# adc_dev.net
KiCad netlist of a schematic drawn in EAGLE
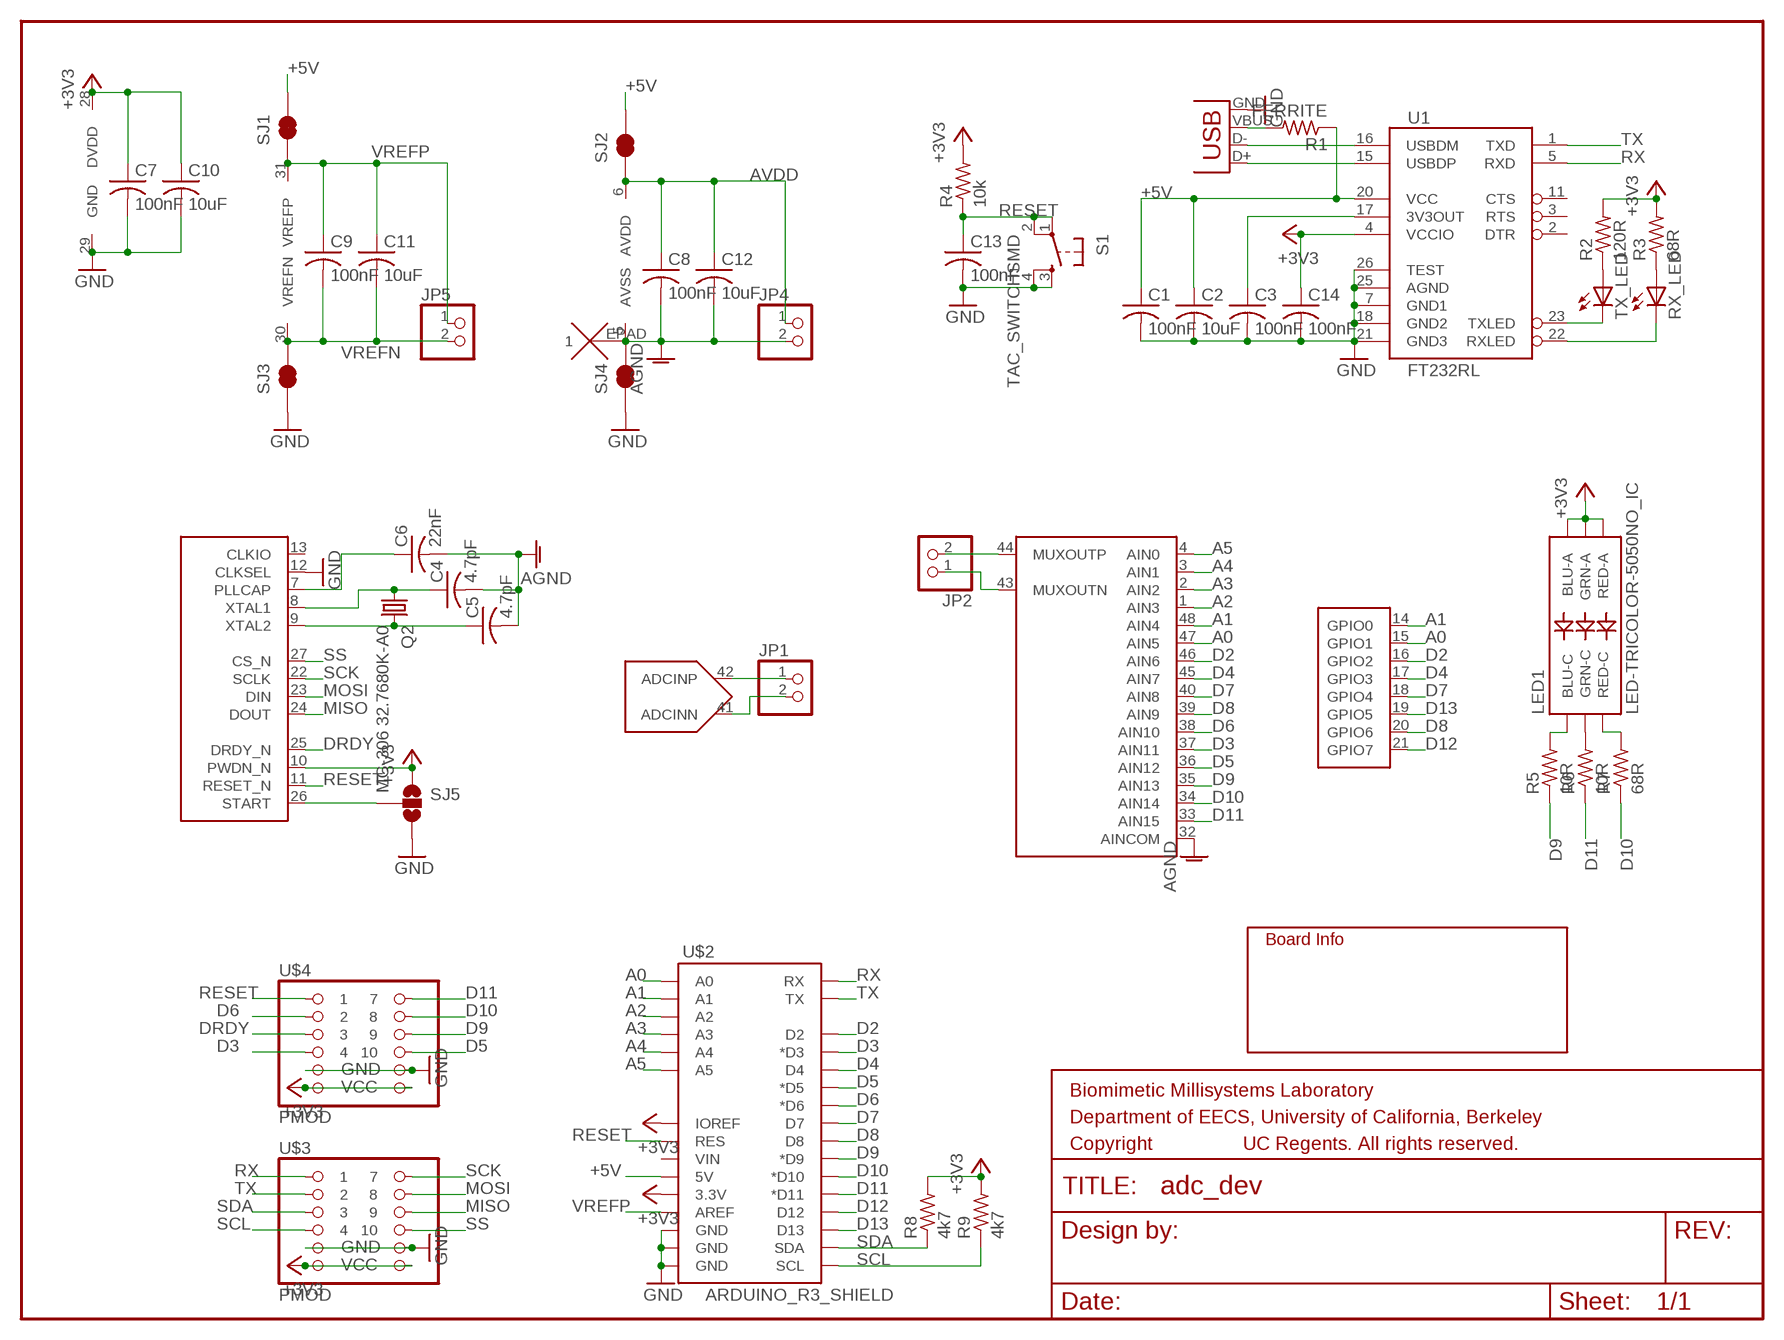
[diagram p0: schematic, sheet 1]

(export (version "E")
  (design (tool "Eeschema 10.0.6"))
  (components
    (comp (ref "C1")
      (value "100nF")
      (footprint "eagle-import:C0603")
      (libsource (lib "eagle-import") (part "C-USC0603"))
    )
    (comp (ref "C2")
      (value "10uF")
      (footprint "eagle-import:C0603")
      (libsource (lib "eagle-import") (part "C-USC0603"))
    )
    (comp (ref "C3")
      (value "100nF")
      (footprint "eagle-import:C0603")
      (libsource (lib "eagle-import") (part "C-USC0603"))
    )
    (comp (ref "C4")
      (value "4.7pF")
      (footprint "eagle-import:C0603")
      (libsource (lib "eagle-import") (part "C-USC0603"))
    )
    (comp (ref "C5")
      (value "4.7pF")
      (footprint "eagle-import:C0603")
      (libsource (lib "eagle-import") (part "C-USC0603"))
    )
    (comp (ref "C6")
      (value "22nF")
      (footprint "eagle-import:C0603")
      (libsource (lib "eagle-import") (part "C-USC0603"))
    )
    (comp (ref "C7")
      (value "100nF")
      (footprint "eagle-import:C0603")
      (libsource (lib "eagle-import") (part "C-USC0603"))
    )
    (comp (ref "C8")
      (value "100nF")
      (footprint "eagle-import:C0603")
      (libsource (lib "eagle-import") (part "C-USC0603"))
    )
    (comp (ref "C9")
      (value "100nF")
      (footprint "eagle-import:C0603")
      (libsource (lib "eagle-import") (part "C-USC0603"))
    )
    (comp (ref "C10")
      (value "10uF")
      (footprint "eagle-import:C0603")
      (libsource (lib "eagle-import") (part "C-USC0603"))
    )
    (comp (ref "C11")
      (value "10uF")
      (footprint "eagle-import:C0603")
      (libsource (lib "eagle-import") (part "C-USC0603"))
    )
    (comp (ref "C12")
      (value "10uF")
      (footprint "eagle-import:C0603")
      (libsource (lib "eagle-import") (part "C-USC0603"))
    )
    (comp (ref "C13")
      (value "100nF")
      (footprint "eagle-import:C0603")
      (libsource (lib "eagle-import") (part "C-USC0603"))
    )
    (comp (ref "C14")
      (value "100nF")
      (footprint "eagle-import:C0603")
      (libsource (lib "eagle-import") (part "C-USC0603"))
    )
    (comp (ref "JP1")
      (value "PINHD-1X2")
      (footprint "eagle-import:1X02")
      (libsource (lib "eagle-import") (part "PINHD-1X2"))
    )
    (comp (ref "JP2")
      (value "PINHD-1X2")
      (footprint "eagle-import:1X02")
      (libsource (lib "eagle-import") (part "PINHD-1X2"))
    )
    (comp (ref "JP3")
      (value "USBSMD")
      (footprint "eagle-import:USB-MINIB")
      (libsource (lib "eagle-import") (part "USBSMD"))
    )
    (comp (ref "JP4")
      (value "PINHD-1X2")
      (footprint "eagle-import:1X02")
      (libsource (lib "eagle-import") (part "PINHD-1X2"))
    )
    (comp (ref "JP5")
      (value "PINHD-1X2")
      (footprint "eagle-import:1X02")
      (libsource (lib "eagle-import") (part "PINHD-1X2"))
    )
    (comp (ref "LED1")
      (value "LED-TRICOLOR-5050NO_IC")
      (footprint "eagle-import:LED-TRICOLOR-5050")
      (libsource (lib "eagle-import") (part "LED-TRICOLOR-5050NO_IC"))
    )
    (comp (ref "Q2")
      (value "MC-306 32.7680K-A0")
      (footprint "eagle-import:MC-306")
      (fields (field (name "MPN") "MC-306 60.0KHZ  100PPM ,12.5PF"))
      (libsource (lib "eagle-import") (part "MC-306"))
    )
    (comp (ref "R1")
      (value "FERRITE")
      (footprint "eagle-import:R0603")
      (libsource (lib "eagle-import") (part "R-US_R0603"))
    )
    (comp (ref "R2")
      (value "120R")
      (footprint "eagle-import:R0603")
      (libsource (lib "eagle-import") (part "R-US_R0603"))
    )
    (comp (ref "R3")
      (value "68R")
      (footprint "eagle-import:R0603")
      (libsource (lib "eagle-import") (part "R-US_R0603"))
    )
    (comp (ref "R4")
      (value "10k")
      (footprint "eagle-import:R0603")
      (libsource (lib "eagle-import") (part "R-US_R0603"))
    )
    (comp (ref "R5")
      (value "10R")
      (footprint "eagle-import:R0603")
      (libsource (lib "eagle-import") (part "R-US_R0603"))
    )
    (comp (ref "R6")
      (value "10R")
      (footprint "eagle-import:R0603")
      (libsource (lib "eagle-import") (part "R-US_R0603"))
    )
    (comp (ref "R7")
      (value "68R")
      (footprint "eagle-import:R0603")
      (libsource (lib "eagle-import") (part "R-US_R0603"))
    )
    (comp (ref "R8")
      (value "4k7")
      (footprint "eagle-import:R0603")
      (libsource (lib "eagle-import") (part "R-US_R0603"))
    )
    (comp (ref "R9")
      (value "4k7")
      (footprint "eagle-import:R0603")
      (libsource (lib "eagle-import") (part "R-US_R0603"))
    )
    (comp (ref "RX_LED")
      (value "LEDCHIPLED_0603")
      (footprint "eagle-import:CHIPLED_0603")
      (libsource (lib "eagle-import") (part "LEDCHIPLED_0603"))
    )
    (comp (ref "S1")
      (value "TAC_SWITCHSMD")
      (footprint "eagle-import:TACTILE_SWITCH_SMD")
      (libsource (lib "eagle-import") (part "TAC_SWITCHSMD"))
    )
    (comp (ref "SJ1")
      (value "JUMPER-PAD-2-NC_BY_TRACE")
      (footprint "eagle-import:PAD-JUMPER-2-NC_BY_TRACE_YES_SILK")
      (libsource (lib "eagle-import") (part "JUMPER-PAD-2-NC_BY_TRACE"))
    )
    (comp (ref "SJ2")
      (value "JUMPER-PAD-2-NC_BY_TRACE")
      (footprint "eagle-import:PAD-JUMPER-2-NC_BY_TRACE_YES_SILK")
      (libsource (lib "eagle-import") (part "JUMPER-PAD-2-NC_BY_TRACE"))
    )
    (comp (ref "SJ3")
      (value "JUMPER-PAD-2-NC_BY_TRACE")
      (footprint "eagle-import:PAD-JUMPER-2-NC_BY_TRACE_YES_SILK")
      (libsource (lib "eagle-import") (part "JUMPER-PAD-2-NC_BY_TRACE"))
    )
    (comp (ref "SJ4")
      (value "JUMPER-PAD-2-NC_BY_TRACE")
      (footprint "eagle-import:PAD-JUMPER-2-NC_BY_TRACE_YES_SILK")
      (libsource (lib "eagle-import") (part "JUMPER-PAD-2-NC_BY_TRACE"))
    )
    (comp (ref "SJ5")
      (value "JUMPER-PAD-3-NOYES_SILK")
      (footprint "eagle-import:PAD-JUMPER-3-NO_YES_SILK")
      (libsource (lib "eagle-import") (part "JUMPER-PAD-3-NOYES_SILK"))
    )
    (comp (ref "TX_LED")
      (value "LEDCHIPLED_0603")
      (footprint "eagle-import:CHIPLED_0603")
      (libsource (lib "eagle-import") (part "LEDCHIPLED_0603"))
    )
    (comp (ref "U$1")
      (value "ADS1258")
      (footprint "eagle-import:QFN-48")
      (libsource (lib "eagle-import") (part "ADS1258"))
    )
    (comp (ref "U$2")
      (value "ARDUINO_R3_SHIELD")
      (footprint "eagle-import:UNO_R3_SHIELD")
      (libsource (lib "eagle-import") (part "ARDUINO_R3_SHIELD"))
    )
    (comp (ref "U$3")
      (value "PMOD")
      (footprint "eagle-import:2X06")
      (libsource (lib "eagle-import") (part "PMOD"))
    )
    (comp (ref "U$4")
      (value "PMOD")
      (footprint "eagle-import:2X06")
      (libsource (lib "eagle-import") (part "PMOD"))
    )
    (comp (ref "U$5")
      (value "INFO")
      (footprint "eagle-import:INFO")
      (fields
        (field (name "AUTHOR") "Austin Buchan")
        (field (name "DATE") "Nov 18, 2014")
        (field (name "DESIGN") "Zedboard Arduino Adapter")
        (field (name "ORGANIZATION") "UC Berkeley ASPIRE")
        (field (name "REVISION") "r0.1")
      )
      (libsource (lib "eagle-import") (part "INFO"))
    )
    (comp (ref "U1")
      (value "FT232RL")
      (footprint "eagle-import:SSOP28DB")
      (libsource (lib "eagle-import") (part "FT232RL-BASICSSOP"))
    )
  )
  (nets
    (net (code "1") (name "+3V3") (class "Default")
      (node (ref "C10") (pin "1") (pinfunction "1_1") (pintype "passive"))
      (node (ref "C14") (pin "1") (pinfunction "1_1") (pintype "passive"))
      (node (ref "C7") (pin "1") (pinfunction "1_1") (pintype "passive"))
      (node (ref "LED1") (pin "1") (pinfunction "GRN-A_1") (pintype "bidirectional"))
      (node (ref "LED1") (pin "2") (pinfunction "RED-A_2") (pintype "bidirectional"))
      (node (ref "LED1") (pin "3") (pinfunction "BLU-A_3") (pintype "bidirectional"))
      (node (ref "R2") (pin "2") (pinfunction "2_2") (pintype "passive"))
      (node (ref "R3") (pin "2") (pinfunction "2_2") (pintype "passive"))
      (node (ref "R4") (pin "2") (pinfunction "2_2") (pintype "passive"))
      (node (ref "R8") (pin "2") (pinfunction "2_2") (pintype "passive"))
      (node (ref "R9") (pin "2") (pinfunction "2_2") (pintype "passive"))
      (node (ref "SJ5") (pin "1") (pinfunction "1_1") (pintype "passive"))
      (node (ref "U$1") (pin "10") (pinfunction "PWDN_N_10") (pintype "bidirectional"))
      (node (ref "U$1") (pin "28") (pinfunction "DVDD_28") (pintype "bidirectional"))
      (node (ref "U$2") (pin "3.3V") (pinfunction "3.3V_3.3V") (pintype "bidirectional"))
      (node (ref "U$2") (pin "IOREF") (pinfunction "IOREF_IOREF") (pintype "bidirectional"))
      (node (ref "U$3") (pin "11") (pinfunction "6_11") (pintype "passive"))
      (node (ref "U$3") (pin "12") (pinfunction "12_12") (pintype "passive"))
      (node (ref "U$4") (pin "11") (pinfunction "6_11") (pintype "passive"))
      (node (ref "U$4") (pin "12") (pinfunction "12_12") (pintype "passive"))
      (node (ref "U1") (pin "4") (pinfunction "VCCIO_4") (pintype "power_in"))
    )
    (net (code "2") (name "/+5V") (class "Default")
      (node (ref "C1") (pin "1") (pinfunction "1_1") (pintype "passive"))
      (node (ref "C2") (pin "1") (pinfunction "1_1") (pintype "passive"))
      (node (ref "R1") (pin "1") (pinfunction "1_1") (pintype "passive"))
      (node (ref "SJ1") (pin "2") (pinfunction "2_2") (pintype "passive"))
      (node (ref "SJ2") (pin "2") (pinfunction "2_2") (pintype "passive"))
      (node (ref "U$2") (pin "5V") (pinfunction "5V_5V") (pintype "bidirectional"))
      (node (ref "U1") (pin "20") (pinfunction "VCC_20") (pintype "power_in"))
    )
    (net (code "3") (name "/A0") (class "Default")
      (node (ref "U$1") (pin "15") (pinfunction "GPIO1_15") (pintype "bidirectional"))
      (node (ref "U$1") (pin "47") (pinfunction "AIN5_47") (pintype "bidirectional"))
      (node (ref "U$2") (pin "A0") (pinfunction "A0_A0") (pintype "bidirectional"))
    )
    (net (code "4") (name "/A1") (class "Default")
      (node (ref "U$1") (pin "14") (pinfunction "GPIO0_14") (pintype "bidirectional"))
      (node (ref "U$1") (pin "48") (pinfunction "AIN4_48") (pintype "bidirectional"))
      (node (ref "U$2") (pin "A1") (pinfunction "A1_A1") (pintype "bidirectional"))
    )
    (net (code "5") (name "/A2") (class "Default")
      (node (ref "U$1") (pin "1") (pinfunction "AIN3_1") (pintype "bidirectional"))
      (node (ref "U$2") (pin "A2") (pinfunction "A2_A2") (pintype "bidirectional"))
    )
    (net (code "6") (name "/A3") (class "Default")
      (node (ref "U$1") (pin "2") (pinfunction "AIN2_2") (pintype "bidirectional"))
      (node (ref "U$2") (pin "A3") (pinfunction "A3_A3") (pintype "bidirectional"))
    )
    (net (code "7") (name "/A4") (class "Default")
      (node (ref "U$1") (pin "3") (pinfunction "AIN1_3") (pintype "bidirectional"))
      (node (ref "U$2") (pin "A4") (pinfunction "A4_A4") (pintype "bidirectional"))
    )
    (net (code "8") (name "/A5") (class "Default")
      (node (ref "U$1") (pin "4") (pinfunction "AIN0_4") (pintype "bidirectional"))
      (node (ref "U$2") (pin "A5") (pinfunction "A5_A5") (pintype "bidirectional"))
    )
    (net (code "9") (name "/AVDD") (class "Default")
      (node (ref "C12") (pin "1") (pinfunction "1_1") (pintype "passive"))
      (node (ref "C8") (pin "1") (pinfunction "1_1") (pintype "passive"))
      (node (ref "JP4") (pin "1") (pinfunction "1_1") (pintype "passive"))
      (node (ref "SJ2") (pin "1") (pinfunction "1_1") (pintype "passive"))
      (node (ref "U$1") (pin "6") (pinfunction "AVDD_6") (pintype "bidirectional"))
    )
    (net (code "10") (name "/D2") (class "Default")
      (node (ref "U$1") (pin "16") (pinfunction "GPIO2_16") (pintype "bidirectional"))
      (node (ref "U$1") (pin "46") (pinfunction "AIN6_46") (pintype "bidirectional"))
      (node (ref "U$2") (pin "D2") (pinfunction "D2_D2") (pintype "bidirectional"))
    )
    (net (code "11") (name "/D3") (class "Default")
      (node (ref "U$1") (pin "37") (pinfunction "AIN11_37") (pintype "bidirectional"))
      (node (ref "U$2") (pin "D3") (pinfunction "*D3_D3") (pintype "bidirectional"))
      (node (ref "U$4") (pin "7") (pinfunction "4_7") (pintype "passive"))
    )
    (net (code "12") (name "/D4") (class "Default")
      (node (ref "U$1") (pin "17") (pinfunction "GPIO3_17") (pintype "bidirectional"))
      (node (ref "U$1") (pin "45") (pinfunction "AIN7_45") (pintype "bidirectional"))
      (node (ref "U$2") (pin "D4") (pinfunction "D4_D4") (pintype "bidirectional"))
    )
    (net (code "13") (name "/D5") (class "Default")
      (node (ref "U$1") (pin "36") (pinfunction "AIN12_36") (pintype "bidirectional"))
      (node (ref "U$2") (pin "D5") (pinfunction "*D5_D5") (pintype "bidirectional"))
      (node (ref "U$4") (pin "8") (pinfunction "10_8") (pintype "passive"))
    )
    (net (code "14") (name "/D6") (class "Default")
      (node (ref "U$1") (pin "38") (pinfunction "AIN10_38") (pintype "bidirectional"))
      (node (ref "U$2") (pin "D6") (pinfunction "*D6_D6") (pintype "bidirectional"))
      (node (ref "U$4") (pin "3") (pinfunction "2_3") (pintype "passive"))
    )
    (net (code "15") (name "/D7") (class "Default")
      (node (ref "U$1") (pin "18") (pinfunction "GPIO4_18") (pintype "bidirectional"))
      (node (ref "U$1") (pin "40") (pinfunction "AIN8_40") (pintype "bidirectional"))
      (node (ref "U$2") (pin "D7") (pinfunction "D7_D7") (pintype "bidirectional"))
    )
    (net (code "16") (name "/D8") (class "Default")
      (node (ref "U$1") (pin "20") (pinfunction "GPIO6_20") (pintype "bidirectional"))
      (node (ref "U$1") (pin "39") (pinfunction "AIN9_39") (pintype "bidirectional"))
      (node (ref "U$2") (pin "D8") (pinfunction "D8_D8") (pintype "bidirectional"))
    )
    (net (code "17") (name "/D9") (class "Default")
      (node (ref "R5") (pin "1") (pinfunction "1_1") (pintype "passive"))
      (node (ref "U$1") (pin "35") (pinfunction "AIN13_35") (pintype "bidirectional"))
      (node (ref "U$2") (pin "D9") (pinfunction "*D9_D9") (pintype "bidirectional"))
      (node (ref "U$4") (pin "6") (pinfunction "9_6") (pintype "passive"))
    )
    (net (code "18") (name "/D10") (class "Default")
      (node (ref "R7") (pin "1") (pinfunction "1_1") (pintype "passive"))
      (node (ref "U$1") (pin "34") (pinfunction "AIN14_34") (pintype "bidirectional"))
      (node (ref "U$2") (pin "D10") (pinfunction "*D10_D10") (pintype "bidirectional"))
      (node (ref "U$4") (pin "4") (pinfunction "8_4") (pintype "passive"))
    )
    (net (code "19") (name "/D11") (class "Default")
      (node (ref "R6") (pin "1") (pinfunction "1_1") (pintype "passive"))
      (node (ref "U$1") (pin "33") (pinfunction "AIN15_33") (pintype "bidirectional"))
      (node (ref "U$2") (pin "D11") (pinfunction "*D11_D11") (pintype "bidirectional"))
      (node (ref "U$4") (pin "2") (pinfunction "7_2") (pintype "passive"))
    )
    (net (code "20") (name "/D12") (class "Default")
      (node (ref "U$1") (pin "21") (pinfunction "GPIO7_21") (pintype "bidirectional"))
      (node (ref "U$2") (pin "D12") (pinfunction "D12_D12") (pintype "bidirectional"))
    )
    (net (code "21") (name "/D13") (class "Default")
      (node (ref "U$1") (pin "19") (pinfunction "GPIO5_19") (pintype "bidirectional"))
      (node (ref "U$2") (pin "D13") (pinfunction "D13_D13") (pintype "bidirectional"))
    )
    (net (code "22") (name "/DRDY") (class "Default")
      (node (ref "U$1") (pin "25") (pinfunction "DRDY_N_25") (pintype "bidirectional"))
      (node (ref "U$4") (pin "5") (pinfunction "3_5") (pintype "passive"))
    )
    (net (code "23") (name "/MISO") (class "Default")
      (node (ref "U$1") (pin "24") (pinfunction "DOUT_24") (pintype "bidirectional"))
      (node (ref "U$3") (pin "6") (pinfunction "9_6") (pintype "passive"))
    )
    (net (code "24") (name "/MOSI") (class "Default")
      (node (ref "U$1") (pin "23") (pinfunction "DIN_23") (pintype "bidirectional"))
      (node (ref "U$3") (pin "4") (pinfunction "8_4") (pintype "passive"))
    )
    (net (code "25") (name "/RESET") (class "Default")
      (node (ref "C13") (pin "1") (pinfunction "1_1") (pintype "passive"))
      (node (ref "R4") (pin "1") (pinfunction "1_1") (pintype "passive"))
      (node (ref "S1") (pin "1") (pinfunction "1_1") (pintype "passive"))
      (node (ref "S1") (pin "2") (pinfunction "2_2") (pintype "passive"))
      (node (ref "U$1") (pin "11") (pinfunction "RESET_N_11") (pintype "bidirectional"))
      (node (ref "U$2") (pin "RES") (pinfunction "RES_RES") (pintype "bidirectional"))
      (node (ref "U$4") (pin "1") (pinfunction "1_1") (pintype "passive"))
    )
    (net (code "26") (name "/RX") (class "Default")
      (node (ref "U$2") (pin "RX") (pinfunction "RX_RX") (pintype "bidirectional"))
      (node (ref "U$3") (pin "1") (pinfunction "1_1") (pintype "passive"))
      (node (ref "U1") (pin "5") (pinfunction "RXD_5") (pintype "input"))
    )
    (net (code "27") (name "/SCK") (class "Default")
      (node (ref "U$1") (pin "22") (pinfunction "SCLK_22") (pintype "bidirectional"))
      (node (ref "U$3") (pin "2") (pinfunction "7_2") (pintype "passive"))
    )
    (net (code "28") (name "/SCL") (class "Default")
      (node (ref "R9") (pin "1") (pinfunction "1_1") (pintype "passive"))
      (node (ref "U$2") (pin "SCL") (pinfunction "SCL_SCL") (pintype "bidirectional"))
      (node (ref "U$3") (pin "7") (pinfunction "4_7") (pintype "passive"))
    )
    (net (code "29") (name "/SDA") (class "Default")
      (node (ref "R8") (pin "1") (pinfunction "1_1") (pintype "passive"))
      (node (ref "U$2") (pin "SDA") (pinfunction "SDA_SDA") (pintype "bidirectional"))
      (node (ref "U$3") (pin "5") (pinfunction "3_5") (pintype "passive"))
    )
    (net (code "30") (name "/SS") (class "Default")
      (node (ref "U$1") (pin "27") (pinfunction "CS_N_27") (pintype "bidirectional"))
      (node (ref "U$3") (pin "8") (pinfunction "10_8") (pintype "passive"))
    )
    (net (code "31") (name "/TX") (class "Default")
      (node (ref "U$2") (pin "TX") (pinfunction "TX_TX") (pintype "bidirectional"))
      (node (ref "U$3") (pin "3") (pinfunction "2_3") (pintype "passive"))
      (node (ref "U1") (pin "1") (pinfunction "TXD_1") (pintype "output"))
    )
    (net (code "32") (name "/VREFN") (class "Default")
      (node (ref "C11") (pin "2") (pinfunction "2_2") (pintype "passive"))
      (node (ref "C9") (pin "2") (pinfunction "2_2") (pintype "passive"))
      (node (ref "JP5") (pin "2") (pinfunction "2_2") (pintype "passive"))
      (node (ref "SJ3") (pin "2") (pinfunction "2_2") (pintype "passive"))
      (node (ref "U$1") (pin "30") (pinfunction "VREFN_30") (pintype "bidirectional"))
    )
    (net (code "33") (name "/VREFP") (class "Default")
      (node (ref "C11") (pin "1") (pinfunction "1_1") (pintype "passive"))
      (node (ref "C9") (pin "1") (pinfunction "1_1") (pintype "passive"))
      (node (ref "JP5") (pin "1") (pinfunction "1_1") (pintype "passive"))
      (node (ref "SJ1") (pin "1") (pinfunction "1_1") (pintype "passive"))
      (node (ref "U$1") (pin "31") (pinfunction "VREFP_31") (pintype "bidirectional"))
      (node (ref "U$2") (pin "AREF") (pinfunction "AREF_AREF") (pintype "bidirectional"))
    )
    (net (code "34") (name "AGND") (class "Default")
      (node (ref "C12") (pin "2") (pinfunction "2_2") (pintype "passive"))
      (node (ref "C4") (pin "2") (pinfunction "2_2") (pintype "passive"))
      (node (ref "C5") (pin "2") (pinfunction "2_2") (pintype "passive"))
      (node (ref "C6") (pin "2") (pinfunction "2_2") (pintype "passive"))
      (node (ref "C8") (pin "2") (pinfunction "2_2") (pintype "passive"))
      (node (ref "JP4") (pin "2") (pinfunction "2_2") (pintype "passive"))
      (node (ref "SJ4") (pin "2") (pinfunction "2_2") (pintype "passive"))
      (node (ref "U$1") (pin "32") (pinfunction "AINCOM_32") (pintype "bidirectional"))
      (node (ref "U$1") (pin "5") (pinfunction "AVSS_5") (pintype "bidirectional"))
      (node (ref "U$1") (pin "EPAD") (pinfunction "1_EPAD") (pintype "bidirectional"))
    )
    (net (code "35") (name "GND") (class "Default")
      (node (ref "C1") (pin "2") (pinfunction "2_2") (pintype "passive"))
      (node (ref "C10") (pin "2") (pinfunction "2_2") (pintype "passive"))
      (node (ref "C13") (pin "2") (pinfunction "2_2") (pintype "passive"))
      (node (ref "C14") (pin "2") (pinfunction "2_2") (pintype "passive"))
      (node (ref "C2") (pin "2") (pinfunction "2_2") (pintype "passive"))
      (node (ref "C3") (pin "2") (pinfunction "2_2") (pintype "passive"))
      (node (ref "C7") (pin "2") (pinfunction "2_2") (pintype "passive"))
      (node (ref "JP3") (pin "GND") (pinfunction "GND_GND") (pintype "bidirectional"))
      (node (ref "S1") (pin "3") (pinfunction "3_3") (pintype "passive"))
      (node (ref "S1") (pin "4") (pinfunction "4_4") (pintype "passive"))
      (node (ref "SJ3") (pin "1") (pinfunction "1_1") (pintype "passive"))
      (node (ref "SJ4") (pin "1") (pinfunction "1_1") (pintype "passive"))
      (node (ref "SJ5") (pin "3") (pinfunction "3_3") (pintype "passive"))
      (node (ref "U$1") (pin "12") (pinfunction "CLKSEL_12") (pintype "bidirectional"))
      (node (ref "U$1") (pin "29") (pinfunction "GND_29") (pintype "bidirectional"))
      (node (ref "U$2") (pin "GND@0") (pinfunction "GND_GND@0") (pintype "bidirectional"))
      (node (ref "U$2") (pin "GND@1") (pinfunction "GND_GND@1") (pintype "bidirectional"))
      (node (ref "U$2") (pin "GND@2") (pinfunction "GND_GND@2") (pintype "bidirectional"))
      (node (ref "U$3") (pin "10") (pinfunction "11_10") (pintype "passive"))
      (node (ref "U$3") (pin "9") (pinfunction "5_9") (pintype "passive"))
      (node (ref "U$4") (pin "10") (pinfunction "11_10") (pintype "passive"))
      (node (ref "U$4") (pin "9") (pinfunction "5_9") (pintype "passive"))
      (node (ref "U1") (pin "18") (pinfunction "GND2_18") (pintype "power_in"))
      (node (ref "U1") (pin "21") (pinfunction "GND3_21") (pintype "power_in"))
      (node (ref "U1") (pin "25") (pinfunction "AGND_25") (pintype "power_in"))
      (node (ref "U1") (pin "26") (pinfunction "TEST_26") (pintype "input"))
      (node (ref "U1") (pin "7") (pinfunction "GND1_7") (pintype "power_in"))
    )
    (net (code "36") (name "Net-(JP3-PadVBUS)") (class "Default")
      (node (ref "JP3") (pin "VBUS") (pinfunction "VBUS_VBUS") (pintype "bidirectional"))
      (node (ref "R1") (pin "2") (pinfunction "2_2") (pintype "passive"))
    )
    (net (code "37") (name "Net-(LED1-BLU-C)") (class "Default")
      (node (ref "LED1") (pin "4") (pinfunction "BLU-C_4") (pintype "bidirectional"))
      (node (ref "R5") (pin "2") (pinfunction "2_2") (pintype "passive"))
    )
    (net (code "38") (name "Net-(LED1-GRN-C)") (class "Default")
      (node (ref "LED1") (pin "6") (pinfunction "GRN-C_6") (pintype "bidirectional"))
      (node (ref "R6") (pin "2") (pinfunction "2_2") (pintype "passive"))
    )
    (net (code "39") (name "Net-(LED1-RED-C)") (class "Default")
      (node (ref "LED1") (pin "5") (pinfunction "RED-C_5") (pintype "bidirectional"))
      (node (ref "R7") (pin "2") (pinfunction "2_2") (pintype "passive"))
    )
    (net (code "40") (name "Net-(Q2-2)") (class "Default")
      (node (ref "C5") (pin "1") (pinfunction "1_1") (pintype "passive"))
      (node (ref "Q2") (pin "4") (pinfunction "2_4") (pintype "passive"))
      (node (ref "U$1") (pin "9") (pinfunction "XTAL2_9") (pintype "bidirectional"))
    )
    (net (code "41") (name "Net-(R2-Pad1)") (class "Default")
      (node (ref "R2") (pin "1") (pinfunction "1_1") (pintype "passive"))
      (node (ref "TX_LED") (pin "A") (pinfunction "A_A") (pintype "passive"))
    )
    (net (code "42") (name "Net-(R3-Pad1)") (class "Default")
      (node (ref "R3") (pin "1") (pinfunction "1_1") (pintype "passive"))
      (node (ref "RX_LED") (pin "A") (pinfunction "A_A") (pintype "passive"))
    )
    (net (code "43") (name "Net-(U$1A-ADCINN)") (class "Default")
      (node (ref "JP1") (pin "2") (pinfunction "2_2") (pintype "passive"))
      (node (ref "U$1") (pin "41") (pinfunction "ADCINN_41") (pintype "bidirectional"))
    )
    (net (code "44") (name "Net-(U$1A-ADCINP)") (class "Default")
      (node (ref "JP1") (pin "1") (pinfunction "1_1") (pintype "passive"))
      (node (ref "U$1") (pin "42") (pinfunction "ADCINP_42") (pintype "bidirectional"))
    )
    (net (code "45") (name "Net-(U$1C-PLLCAP)") (class "Default")
      (node (ref "C6") (pin "1") (pinfunction "1_1") (pintype "passive"))
      (node (ref "U$1") (pin "7") (pinfunction "PLLCAP_7") (pintype "bidirectional"))
    )
    (net (code "46") (name "Net-(U$1C-START)") (class "Default")
      (node (ref "SJ5") (pin "2") (pinfunction "2_2") (pintype "passive"))
      (node (ref "U$1") (pin "26") (pinfunction "START_26") (pintype "bidirectional"))
    )
    (net (code "47") (name "Net-(U$1C-XTAL1)") (class "Default")
      (node (ref "C4") (pin "1") (pinfunction "1_1") (pintype "passive"))
      (node (ref "Q2") (pin "1") (pinfunction "1_1") (pintype "passive"))
      (node (ref "U$1") (pin "8") (pinfunction "XTAL1_8") (pintype "bidirectional"))
    )
    (net (code "48") (name "Net-(U$1G-MUXOUTN)") (class "Default")
      (node (ref "JP2") (pin "1") (pinfunction "1_1") (pintype "passive"))
      (node (ref "U$1") (pin "43") (pinfunction "MUXOUTN_43") (pintype "bidirectional"))
    )
    (net (code "49") (name "Net-(U$1G-MUXOUTP)") (class "Default")
      (node (ref "JP2") (pin "2") (pinfunction "2_2") (pintype "passive"))
      (node (ref "U$1") (pin "44") (pinfunction "MUXOUTP_44") (pintype "bidirectional"))
    )
    (net (code "50") (name "Net-(U1-3V3OUT)") (class "Default")
      (node (ref "C3") (pin "1") (pinfunction "1_1") (pintype "passive"))
      (node (ref "U1") (pin "17") (pinfunction "3V3OUT_17") (pintype "output"))
    )
    (net (code "51") (name "Net-(U1-RXLED)") (class "Default")
      (node (ref "RX_LED") (pin "C") (pinfunction "C_C") (pintype "passive"))
      (node (ref "U1") (pin "22") (pinfunction "RXLED_22") (pintype "bidirectional"))
    )
    (net (code "52") (name "Net-(U1-TXLED)") (class "Default")
      (node (ref "TX_LED") (pin "C") (pinfunction "C_C") (pintype "passive"))
      (node (ref "U1") (pin "23") (pinfunction "TXLED_23") (pintype "bidirectional"))
    )
    (net (code "53") (name "Net-(U1-USBDM)") (class "Default")
      (node (ref "JP3") (pin "D-") (pinfunction "D-_D-") (pintype "bidirectional"))
      (node (ref "U1") (pin "16") (pinfunction "USBDM_16") (pintype "bidirectional"))
    )
    (net (code "54") (name "Net-(U1-USBDP)") (class "Default")
      (node (ref "JP3") (pin "D+") (pinfunction "D+_D+") (pintype "bidirectional"))
      (node (ref "U1") (pin "15") (pinfunction "USBDP_15") (pintype "bidirectional"))
    )
    (net (code "55") (name "unconnected-(U$1C-CLKIO-Pad13)") (class "Default")
      (node (ref "U$1") (pin "13") (pinfunction "CLKIO_13") (pintype "bidirectional"))
    )
    (net (code "56") (name "unconnected-(U$2-PadVIN)") (class "Default")
      (node (ref "U$2") (pin "VIN") (pinfunction "VIN_VIN") (pintype "bidirectional"))
    )
    (net (code "57") (name "unconnected-(U1-CTS-Pad11)") (class "Default")
      (node (ref "U1") (pin "11") (pinfunction "CTS_11") (pintype "bidirectional"))
    )
    (net (code "58") (name "unconnected-(U1-DTR-Pad2)") (class "Default")
      (node (ref "U1") (pin "2") (pinfunction "DTR_2") (pintype "bidirectional"))
    )
    (net (code "59") (name "unconnected-(U1-RTS-Pad3)") (class "Default")
      (node (ref "U1") (pin "3") (pinfunction "RTS_3") (pintype "bidirectional"))
    )
  )
)
